# L-1K1W1007851A.net
KiCad netlist of a schematic drawn in Altium Designer
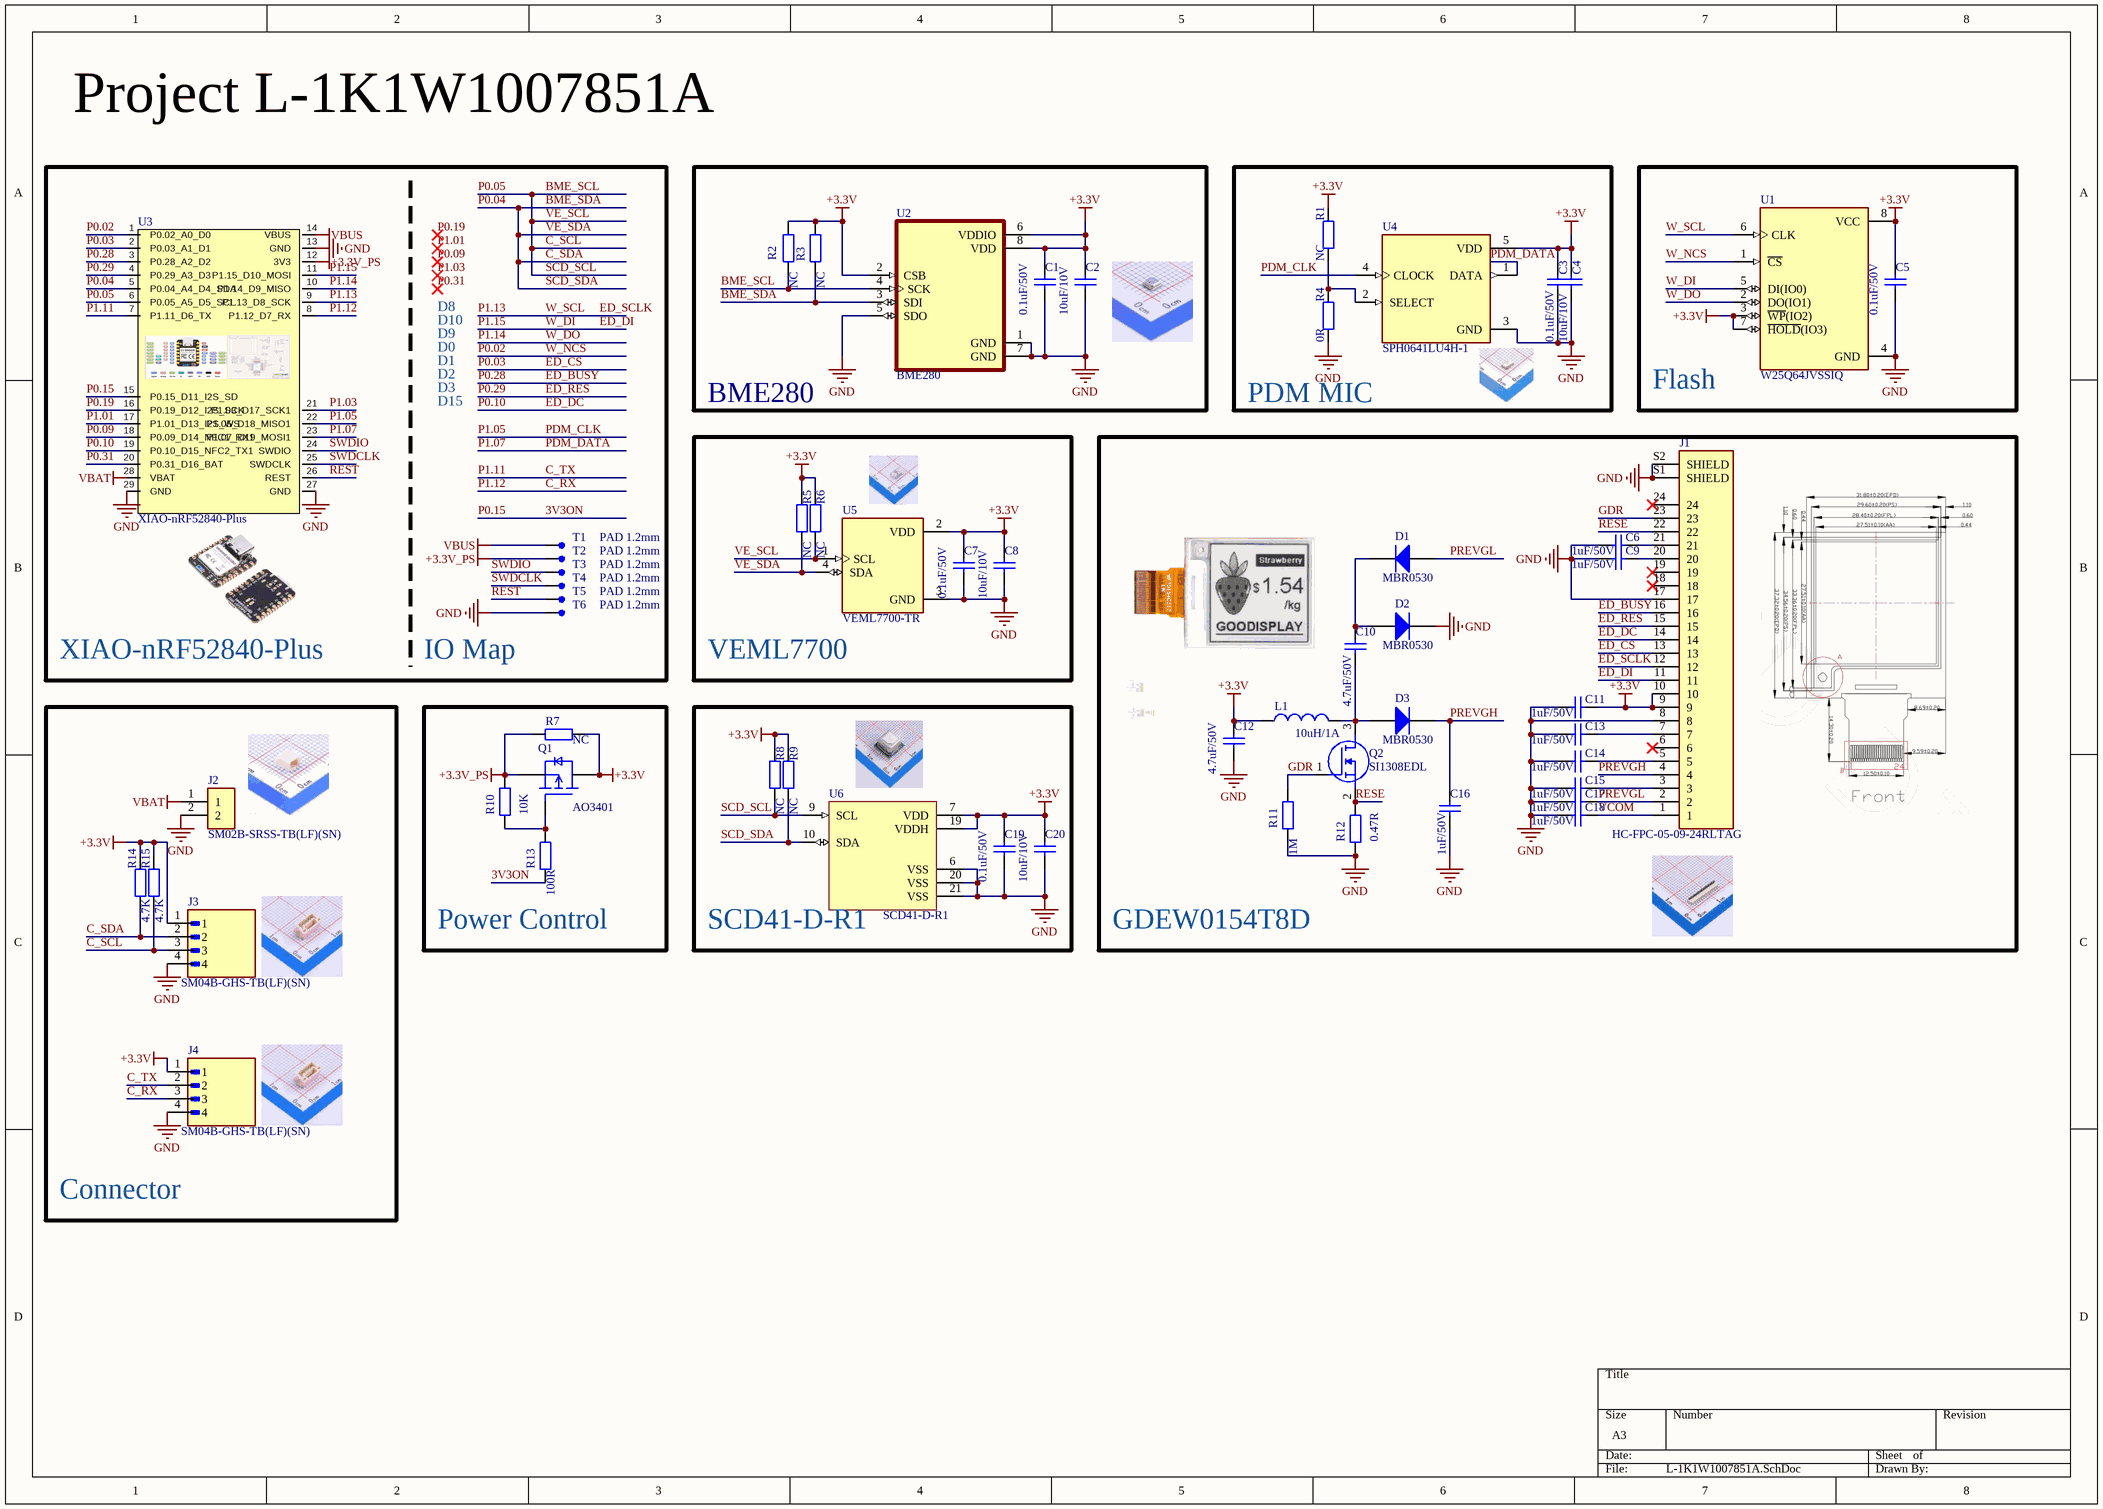
[diagram p0: L-1K1W1007851A.SchDoc]

(export (version "E")
  (design (tool "Eeschema 10.0.6"))
  (components
    (comp (ref "C1") (value "0.1uF/50V") (footprint "C 0603") (libsource (lib "QT") (part "CAP")))
    (comp (ref "C2") (value "10uF/10V") (footprint "C 0603") (libsource (lib "QT") (part "CAP")))
    (comp (ref "C3") (value "0.1uF/50V") (footprint "C 0603") (libsource (lib "QT") (part "CAP")))
    (comp (ref "C4") (value "10uF/10V") (footprint "C 0603") (libsource (lib "QT") (part "CAP")))
    (comp (ref "C5") (value "0.1uF/50V") (footprint "C 0603") (libsource (lib "QT") (part "CAP")))
    (comp (ref "C6") (value "1uF/50V") (footprint "C 0603") (libsource (lib "QT") (part "CAP")))
    (comp (ref "C7") (value "0.1uF/50V") (footprint "C 0603") (libsource (lib "QT") (part "CAP")))
    (comp (ref "C8") (value "10uF/10V") (footprint "C 0603") (libsource (lib "QT") (part "CAP")))
    (comp (ref "C9") (value "1uF/50V") (footprint "C 0603") (libsource (lib "QT") (part "CAP")))
    (comp (ref "C10") (value "4.7uF/50V") (footprint "C 0805") (libsource (lib "QT") (part "CAP")))
    (comp (ref "C11") (value "1uF/50V") (footprint "C 0603") (libsource (lib "QT") (part "CAP")))
    (comp (ref "C12") (value "4.7uF/50V") (footprint "C 0805") (libsource (lib "QT") (part "CAP")))
    (comp (ref "C13") (value "1uF/50V") (footprint "C 0603") (libsource (lib "QT") (part "CAP")))
    (comp (ref "C14") (value "1uF/50V") (footprint "C 0603") (libsource (lib "QT") (part "CAP")))
    (comp (ref "C15") (value "1uF/50V") (footprint "C 0603") (libsource (lib "QT") (part "CAP")))
    (comp (ref "C16") (value "1uF/50V") (footprint "C 0603") (libsource (lib "QT") (part "CAP")))
    (comp (ref "C17") (value "1uF/50V") (footprint "C 0603") (libsource (lib "QT") (part "CAP")))
    (comp (ref "C18") (value "1uF/50V") (footprint "C 0603") (libsource (lib "QT") (part "CAP")))
    (comp (ref "C19") (value "0.1uF/50V") (footprint "C 0603") (libsource (lib "QT") (part "CAP")))
    (comp (ref "C20") (value "10uF/10V") (footprint "C 0603") (libsource (lib "QT") (part "CAP")))
    (comp (ref "D1")
      (value "MBR0530")
      (footprint "SOD-323")
      (description "High Conductance Fast Diode")
      (fields (field (name "PUBLISHER") "Altium Limited"))
      (libsource (lib "QT") (part "D 1N4148"))
    )
    (comp (ref "D2")
      (value "MBR0530")
      (footprint "SOD-323")
      (description "High Conductance Fast Diode")
      (fields (field (name "PUBLISHER") "Altium Limited"))
      (libsource (lib "QT") (part "D 1N4148"))
    )
    (comp (ref "D3")
      (value "MBR0530")
      (footprint "SOD-323")
      (description "High Conductance Fast Diode")
      (fields (field (name "PUBLISHER") "Altium Limited"))
      (libsource (lib "QT") (part "D 1N4148"))
    )
    (comp (ref "J1")
      (value "HC-FPC-05-09-24RLTAG")
      (footprint "GCT_FFC2B28-24-G")
      (description "24 Position FFC, FPC Connector Contacts, Top and Bottom 0.020 (0.50mm) Surface Mount, Right Angle")
      (fields (field (name "MF") "Global Connector Technology") (field (name "MP") "FFC2B28-24-G"))
      (libsource (lib "FFC2B28-24-G") (part "FFC2B28-24-G"))
    )
    (comp (ref "J2")
      (value "SM02B-SRSS-TB(LF)(SN)")
      (footprint "SM02B-SRSS-TB(LF)(SN)")
      (description "Connector Header Surface Mount, Right Angle 2 position 0.039 (1.00mm)")
      (fields (field (name "MF") "JST Sales"))
      (libsource (lib "SM02B-SRSS-TB(LF)(SN)") (part "SM02B-SRSS-TB(LF)(SN)"))
    )
    (comp (ref "J3")
      (value "SM04B-GHS-TB(LF)(SN)")
      (footprint "JST_SM04B-SRSS-TB(LF)(SN)")
      (description "Connector Header Surface Mount, Right Angle 4 position 0.049 (1.25mm)")
      (fields (field (name "MF") "JST Sales America Inc."))
      (libsource (lib "SM04B-GHS-TB(LF)(SN)") (part "SM04B-GHS-TB(LF)(SN)"))
    )
    (comp (ref "J4")
      (value "SM04B-GHS-TB(LF)(SN)")
      (footprint "JST_SM04B-SRSS-TB(LF)(SN)")
      (description "Connector Header Surface Mount, Right Angle 4 position 0.049 (1.25mm)")
      (fields (field (name "MF") "JST Sales America Inc."))
      (libsource (lib "SM04B-GHS-TB(LF)(SN)") (part "SM04B-GHS-TB(LF)(SN)"))
    )
    (comp (ref "L1") (value "10uH/1A") (footprint "CD31") (libsource (lib "QT") (part "INDUCTOR")))
    (comp (ref "Q1")
      (value "AO3401")
      (footprint "SOT23-3N")
      (description "P-Channel 30 V 4A (Ta) 1.4W (Ta) Surface Mount SOT-23-3")
      (fields (field (name "MF") "Alpha & Omega Semiconductor"))
      (libsource (lib "AO3401") (part "AO3401"))
    )
    (comp (ref "Q2")
      (value "SI1308EDL")
      (footprint "SOT323")
      (description "N-Channel 30 V 5.8A (Ta) 1.4W (Ta) Surface Mount SOT-23-3")
      (fields (field (name "MF") "Alpha &") (field (name "MP") "AO3400"))
      (libsource (lib "AO3400") (part "AO3400"))
    )
    (comp (ref "R1")
      (value "NC")
      (footprint "R 0603")
      (description "Resistor")
      (fields (field (name "PUBLISHER") "Altium Limited"))
      (libsource (lib "QT") (part "RES2"))
    )
    (comp (ref "R2")
      (value "NC")
      (footprint "R 0603")
      (description "Resistor")
      (fields (field (name "PUBLISHER") "Altium Limited"))
      (libsource (lib "QT") (part "RES2"))
    )
    (comp (ref "R3")
      (value "NC")
      (footprint "R 0603")
      (description "Resistor")
      (fields (field (name "PUBLISHER") "Altium Limited"))
      (libsource (lib "QT") (part "RES2"))
    )
    (comp (ref "R4")
      (value "0R")
      (footprint "R 0603")
      (description "Resistor")
      (fields (field (name "PUBLISHER") "Altium Limited"))
      (libsource (lib "QT") (part "RES2"))
    )
    (comp (ref "R5")
      (value "NC")
      (footprint "R 0603")
      (description "Resistor")
      (fields (field (name "PUBLISHER") "Altium Limited"))
      (libsource (lib "QT") (part "RES2"))
    )
    (comp (ref "R6")
      (value "NC")
      (footprint "R 0603")
      (description "Resistor")
      (fields (field (name "PUBLISHER") "Altium Limited"))
      (libsource (lib "QT") (part "RES2"))
    )
    (comp (ref "R7")
      (value "NC")
      (footprint "R 0603")
      (description "Resistor")
      (fields (field (name "PUBLISHER") "Altium Limited"))
      (libsource (lib "") (part "RES2_1"))
    )
    (comp (ref "R8")
      (value "NC")
      (footprint "R 0603")
      (description "Resistor")
      (fields (field (name "PUBLISHER") "Altium Limited"))
      (libsource (lib "QT") (part "RES2"))
    )
    (comp (ref "R9")
      (value "NC")
      (footprint "R 0603")
      (description "Resistor")
      (fields (field (name "PUBLISHER") "Altium Limited"))
      (libsource (lib "QT") (part "RES2"))
    )
    (comp (ref "R10")
      (value "10K")
      (footprint "R 0603")
      (description "Resistor")
      (fields (field (name "PUBLISHER") "Altium Limited"))
      (libsource (lib "QT") (part "RES2"))
    )
    (comp (ref "R11")
      (value "1M")
      (footprint "R 0603")
      (description "Resistor")
      (fields (field (name "PUBLISHER") "Altium Limited"))
      (libsource (lib "QT") (part "RES2"))
    )
    (comp (ref "R12")
      (value "0.47R")
      (footprint "R 0603")
      (description "Resistor")
      (fields (field (name "PUBLISHER") "Altium Limited"))
      (libsource (lib "QT") (part "RES2"))
    )
    (comp (ref "R13")
      (value "100R")
      (footprint "R 0603")
      (description "Resistor")
      (fields (field (name "PUBLISHER") "Altium Limited"))
      (libsource (lib "QT") (part "RES2"))
    )
    (comp (ref "R14")
      (value "4.7K")
      (footprint "R 0603")
      (description "Resistor")
      (fields (field (name "PUBLISHER") "Altium Limited"))
      (libsource (lib "QT") (part "RES2"))
    )
    (comp (ref "R15")
      (value "4.7K")
      (footprint "R 0603")
      (description "Resistor")
      (fields (field (name "PUBLISHER") "Altium Limited"))
      (libsource (lib "QT") (part "RES2"))
    )
    (comp (ref "T1") (value "PAD 1.2mm") (footprint "TEST 1.2") (libsource (lib "常用元件库") (part "TEST")))
    (comp (ref "T2") (value "PAD 1.2mm") (footprint "TEST 1.2") (libsource (lib "常用元件库") (part "TEST")))
    (comp (ref "T3") (value "PAD 1.2mm") (footprint "TEST 1.2") (libsource (lib "常用元件库") (part "TEST")))
    (comp (ref "T4") (value "PAD 1.2mm") (footprint "TEST 1.2") (libsource (lib "常用元件库") (part "TEST")))
    (comp (ref "T5") (value "PAD 1.2mm") (footprint "TEST 1.2") (libsource (lib "常用元件库") (part "TEST")))
    (comp (ref "T6") (value "PAD 1.2mm") (footprint "TEST 1.2") (libsource (lib "常用元件库") (part "TEST")))
    (comp (ref "U1")
      (value "W25Q64JVSSIQ")
      (footprint "SOIC127P790X216-8N")
      (description "FLASH - NOR Memory IC 64Mb (8M x 8) SPI 80 MHz 8-SOIC")
      (fields (field (name "MF") "Winbond Electronics") (field (name "MP") "W25Q64BVSSIG"))
      (libsource (lib "W25Q64BVSSIG") (part "W25Q64BVSSIG"))
    )
    (comp (ref "U2")
      (value "BME280")
      (footprint "PSON65P250X250X100-8N")
      (libsource (lib "BME280") (part "BME280"))
    )
    (comp (ref "U3")
      (value "XIAO-nRF52840-Plus")
      (footprint "XIAO-nRF52840-Plus")
      (libsource (lib "XIAO-nRF52840-Plus") (part "XIAO-nRF52840-Plus"))
    )
    (comp (ref "U4")
      (value "SPH0641LU4H-1")
      (footprint "MIC_SPH0641LU4H-1")
      (fields (field (name "MF") "Knowles"))
      (libsource (lib "SPH0641LU4H-1") (part "SPH0641LU4H-1"))
    )
    (comp (ref "U5")
      (value "VEML7700-TR")
      (footprint "XDCR_VEML7700-TR")
      (description "Optical Sensor Ambient 545nm I2C 4-SMD, J-Lead")
      (fields (field (name "MF") "Vishay"))
      (libsource (lib "VEML7700-TR") (part "VEML7700-TR"))
    )
    (comp (ref "U6") (value "SCD41-D-R1") (footprint "SCD4x") (libsource (lib "SCD41-D-R1") (part "SCD4x")))
  )
  (nets
    (net (code "1") (name "+3.3V") (class "Default")
      (node (ref "C1") (pin "2") (pinfunction "2_2") (pintype "passive"))
      (node (ref "C11") (pin "1") (pinfunction "1_1") (pintype "passive"))
      (node (ref "C12") (pin "2") (pinfunction "2_2") (pintype "passive"))
      (node (ref "C19") (pin "2") (pinfunction "2_2") (pintype "passive"))
      (node (ref "C2") (pin "2") (pinfunction "2_2") (pintype "passive"))
      (node (ref "C20") (pin "2") (pinfunction "2_2") (pintype "passive"))
      (node (ref "C3") (pin "2") (pinfunction "2_2") (pintype "passive"))
      (node (ref "C4") (pin "2") (pinfunction "2_2") (pintype "passive"))
      (node (ref "C5") (pin "2") (pinfunction "2_2") (pintype "passive"))
      (node (ref "C7") (pin "2") (pinfunction "2_2") (pintype "passive"))
      (node (ref "C8") (pin "2") (pinfunction "2_2") (pintype "passive"))
      (node (ref "J1") (pin "10") (pinfunction "10_10") (pintype "passive"))
      (node (ref "J1") (pin "9") (pinfunction "9_9") (pintype "passive"))
      (node (ref "J3") (pin "1") (pinfunction "1_1") (pintype "passive"))
      (node (ref "J4") (pin "1") (pinfunction "1_1") (pintype "passive"))
      (node (ref "L1") (pin "1") (pinfunction "1_1") (pintype "passive"))
      (node (ref "Q1") (pin "3") (pinfunction "D_3") (pintype "passive"))
      (node (ref "R1") (pin "1") (pinfunction "1_1") (pintype "passive"))
      (node (ref "R14") (pin "1") (pinfunction "1_1") (pintype "passive"))
      (node (ref "R15") (pin "1") (pinfunction "1_1") (pintype "passive"))
      (node (ref "R2") (pin "1") (pinfunction "1_1") (pintype "passive"))
      (node (ref "R3") (pin "1") (pinfunction "1_1") (pintype "passive"))
      (node (ref "R5") (pin "1") (pinfunction "1_1") (pintype "passive"))
      (node (ref "R6") (pin "1") (pinfunction "1_1") (pintype "passive"))
      (node (ref "R7") (pin "2") (pinfunction "2_2") (pintype "passive"))
      (node (ref "R8") (pin "1") (pinfunction "1_1") (pintype "passive"))
      (node (ref "R9") (pin "1") (pinfunction "1_1") (pintype "passive"))
      (node (ref "U1") (pin "3") (pinfunction "~{WP}(IO2)_3") (pintype "bidirectional"))
      (node (ref "U1") (pin "7") (pinfunction "~{HOLD}(IO3)_7") (pintype "bidirectional"))
      (node (ref "U1") (pin "8") (pinfunction "VCC_8") (pintype "power_in"))
      (node (ref "U2") (pin "2") (pinfunction "CSB_2") (pintype "input"))
      (node (ref "U2") (pin "6") (pinfunction "VDDIO_6") (pintype "power_in"))
      (node (ref "U2") (pin "8") (pinfunction "VDD_8") (pintype "power_in"))
      (node (ref "U4") (pin "5") (pinfunction "VDD_5") (pintype "power_in"))
      (node (ref "U5") (pin "2") (pinfunction "VDD_2") (pintype "power_in"))
      (node (ref "U6") (pin "19") (pinfunction "VDDH_19") (pintype "power_in"))
      (node (ref "U6") (pin "7") (pinfunction "VDD_7") (pintype "power_in"))
    )
    (net (code "2") (name "+3.3V_PS") (class "Default")
      (node (ref "Q1") (pin "2") (pinfunction "S_2") (pintype "passive"))
      (node (ref "R10") (pin "1") (pinfunction "1_1") (pintype "passive"))
      (node (ref "R7") (pin "1") (pinfunction "1_1") (pintype "passive"))
      (node (ref "T2") (pin "1") (pintype "passive"))
      (node (ref "U3") (pin "12") (pinfunction "3V3_12") (pintype "passive"))
    )
    (net (code "3") (name "/3V3ON") (class "Default")
      (node (ref "R13") (pin "2") (pinfunction "2_2") (pintype "passive"))
      (node (ref "U3") (pin "15") (pinfunction "P0.15_D11_I2S_SD_15") (pintype "passive"))
    )
    (net (code "4") (name "/BME_SCL") (class "Default")
      (node (ref "J3") (pin "3") (pinfunction "3_3") (pintype "passive"))
      (node (ref "R14") (pin "2") (pinfunction "2_2") (pintype "passive"))
      (node (ref "R2") (pin "2") (pinfunction "2_2") (pintype "passive"))
      (node (ref "R6") (pin "2") (pinfunction "2_2") (pintype "passive"))
      (node (ref "R8") (pin "2") (pinfunction "2_2") (pintype "passive"))
      (node (ref "U2") (pin "4") (pinfunction "SCK_4") (pintype "input"))
      (node (ref "U3") (pin "6") (pinfunction "P0.05_A5_D5_SCL_6") (pintype "passive"))
      (node (ref "U5") (pin "1") (pinfunction "SCL_1") (pintype "input"))
      (node (ref "U6") (pin "9") (pinfunction "SCL_9") (pintype "input"))
    )
    (net (code "5") (name "/BME_SDA") (class "Default")
      (node (ref "J3") (pin "2") (pinfunction "2_2") (pintype "passive"))
      (node (ref "R15") (pin "2") (pinfunction "2_2") (pintype "passive"))
      (node (ref "R3") (pin "2") (pinfunction "2_2") (pintype "passive"))
      (node (ref "R5") (pin "2") (pinfunction "2_2") (pintype "passive"))
      (node (ref "R9") (pin "2") (pinfunction "2_2") (pintype "passive"))
      (node (ref "U2") (pin "3") (pinfunction "SDI_3") (pintype "bidirectional"))
      (node (ref "U3") (pin "5") (pinfunction "P0.04_A4_D4_SDA_5") (pintype "passive"))
      (node (ref "U5") (pin "4") (pinfunction "SDA_4") (pintype "bidirectional"))
      (node (ref "U6") (pin "10") (pinfunction "SDA_10") (pintype "bidirectional"))
    )
    (net (code "6") (name "/C_RX") (class "Default")
      (node (ref "J4") (pin "3") (pinfunction "3_3") (pintype "passive"))
      (node (ref "U3") (pin "8") (pinfunction "P1.12_D7_RX_8") (pintype "passive"))
    )
    (net (code "7") (name "/C_TX") (class "Default")
      (node (ref "J4") (pin "2") (pinfunction "2_2") (pintype "passive"))
      (node (ref "U3") (pin "7") (pinfunction "P1.11_D6_TX_7") (pintype "passive"))
    )
    (net (code "8") (name "/ED_BUSY") (class "Default")
      (node (ref "J1") (pin "16") (pinfunction "16_16") (pintype "passive"))
      (node (ref "U3") (pin "3") (pinfunction "P0.28_A2_D2_3") (pintype "passive"))
    )
    (net (code "9") (name "/ED_CS") (class "Default")
      (node (ref "J1") (pin "13") (pinfunction "13_13") (pintype "passive"))
      (node (ref "U3") (pin "2") (pinfunction "P0.03_A1_D1_2") (pintype "passive"))
    )
    (net (code "10") (name "/ED_DC") (class "Default")
      (node (ref "J1") (pin "14") (pinfunction "14_14") (pintype "passive"))
      (node (ref "U3") (pin "19") (pinfunction "P0.10_D15_NFC2_TX1_19") (pintype "passive"))
    )
    (net (code "11") (name "/ED_DI") (class "Default")
      (node (ref "J1") (pin "11") (pinfunction "11_11") (pintype "passive"))
      (node (ref "U1") (pin "5") (pinfunction "DI(IO0)_5") (pintype "bidirectional"))
      (node (ref "U3") (pin "11") (pinfunction "P1.15_D10_MOSI_11") (pintype "passive"))
    )
    (net (code "12") (name "/ED_RES") (class "Default")
      (node (ref "J1") (pin "15") (pinfunction "15_15") (pintype "passive"))
      (node (ref "U3") (pin "4") (pinfunction "P0.29_A3_D3_4") (pintype "passive"))
    )
    (net (code "13") (name "/ED_SCLK") (class "Default")
      (node (ref "J1") (pin "12") (pinfunction "12_12") (pintype "passive"))
      (node (ref "U1") (pin "6") (pinfunction "CLK_6") (pintype "input"))
      (node (ref "U3") (pin "9") (pinfunction "P1.13_D8_SCK_9") (pintype "passive"))
    )
    (net (code "14") (name "/GDR") (class "Default")
      (node (ref "J1") (pin "23") (pinfunction "23_23") (pintype "passive"))
      (node (ref "Q2") (pin "1") (pinfunction "G_1") (pintype "passive"))
      (node (ref "R11") (pin "1") (pinfunction "1_1") (pintype "passive"))
    )
    (net (code "15") (name "/P0.02") (class "Default")
      (node (ref "U1") (pin "1") (pinfunction "~{CS}_1") (pintype "input"))
      (node (ref "U3") (pin "1") (pinfunction "P0.02_A0_D0_1") (pintype "passive"))
    )
    (net (code "16") (name "/P0.09") (class "Default")
      (node (ref "U3") (pin "18") (pinfunction "P0.09_D14_NFC1_RX1_18") (pintype "passive+no_connect"))
    )
    (net (code "17") (name "/P0.19") (class "Default")
      (node (ref "U3") (pin "16") (pinfunction "P0.19_D12_I2S_SCK_16") (pintype "passive+no_connect"))
    )
    (net (code "18") (name "/P0.31") (class "Default")
      (node (ref "U3") (pin "20") (pinfunction "P0.31_D16_BAT_20") (pintype "passive+no_connect"))
    )
    (net (code "19") (name "/P1.01") (class "Default")
      (node (ref "U3") (pin "17") (pinfunction "P1.01_D13_I2S_WS_17") (pintype "passive+no_connect"))
    )
    (net (code "20") (name "/P1.03") (class "Default")
      (node (ref "U3") (pin "21") (pinfunction "P1.03_D17_SCK1_21") (pintype "passive+no_connect"))
    )
    (net (code "21") (name "/P1.05") (class "Default")
      (node (ref "U3") (pin "22") (pinfunction "P1.05_D18_MISO1_22") (pintype "passive"))
      (node (ref "U4") (pin "4") (pinfunction "CLOCK_4") (pintype "input"))
    )
    (net (code "22") (name "/P1.07") (class "Default")
      (node (ref "U3") (pin "23") (pinfunction "P1.07_D19_MOSI1_23") (pintype "passive"))
      (node (ref "U4") (pin "1") (pinfunction "DATA_1") (pintype "output"))
    )
    (net (code "23") (name "/P1.14") (class "Default")
      (node (ref "U1") (pin "2") (pinfunction "DO(IO1)_2") (pintype "bidirectional"))
      (node (ref "U3") (pin "10") (pinfunction "P1.14_D9_MISO_10") (pintype "passive"))
    )
    (net (code "24") (name "/PREVGH") (class "Default")
      (node (ref "C16") (pin "2") (pinfunction "2_2") (pintype "passive"))
      (node (ref "D3") (pin "2") (pinfunction "K_2") (pintype "passive"))
      (node (ref "J1") (pin "4") (pinfunction "4_4") (pintype "passive"))
    )
    (net (code "25") (name "/PREVGL") (class "Default")
      (node (ref "C17") (pin "1") (pinfunction "1_1") (pintype "passive"))
      (node (ref "D1") (pin "1") (pinfunction "A_1") (pintype "passive"))
      (node (ref "J1") (pin "2") (pinfunction "2_2") (pintype "passive"))
    )
    (net (code "26") (name "/RESE") (class "Default")
      (node (ref "J1") (pin "22") (pinfunction "22_22") (pintype "passive"))
      (node (ref "Q2") (pin "2") (pinfunction "S_2") (pintype "passive"))
      (node (ref "R12") (pin "1") (pinfunction "1_1") (pintype "passive"))
    )
    (net (code "27") (name "/REST") (class "Default")
      (node (ref "T5") (pin "1") (pintype "passive"))
      (node (ref "U3") (pin "26") (pinfunction "REST_26") (pintype "passive"))
    )
    (net (code "28") (name "/SWDCLK") (class "Default")
      (node (ref "T4") (pin "1") (pintype "passive"))
      (node (ref "U3") (pin "25") (pinfunction "SWDCLK_25") (pintype "passive"))
    )
    (net (code "29") (name "/SWDIO") (class "Default")
      (node (ref "T3") (pin "1") (pintype "passive"))
      (node (ref "U3") (pin "24") (pinfunction "SWDIO_24") (pintype "passive"))
    )
    (net (code "30") (name "/VCOM") (class "Default")
      (node (ref "C18") (pin "1") (pinfunction "1_1") (pintype "passive"))
      (node (ref "J1") (pin "1") (pinfunction "1_1") (pintype "passive"))
    )
    (net (code "31") (name "GND") (class "Default")
      (node (ref "C1") (pin "1") (pinfunction "1_1") (pintype "passive"))
      (node (ref "C11") (pin "2") (pinfunction "2_2") (pintype "passive"))
      (node (ref "C12") (pin "1") (pinfunction "1_1") (pintype "passive"))
      (node (ref "C13") (pin "2") (pinfunction "2_2") (pintype "passive"))
      (node (ref "C14") (pin "2") (pinfunction "2_2") (pintype "passive"))
      (node (ref "C15") (pin "2") (pinfunction "2_2") (pintype "passive"))
      (node (ref "C16") (pin "1") (pinfunction "1_1") (pintype "passive"))
      (node (ref "C17") (pin "2") (pinfunction "2_2") (pintype "passive"))
      (node (ref "C18") (pin "2") (pinfunction "2_2") (pintype "passive"))
      (node (ref "C19") (pin "1") (pinfunction "1_1") (pintype "passive"))
      (node (ref "C2") (pin "1") (pinfunction "1_1") (pintype "passive"))
      (node (ref "C20") (pin "1") (pinfunction "1_1") (pintype "passive"))
      (node (ref "C3") (pin "1") (pinfunction "1_1") (pintype "passive"))
      (node (ref "C4") (pin "1") (pinfunction "1_1") (pintype "passive"))
      (node (ref "C5") (pin "1") (pinfunction "1_1") (pintype "passive"))
      (node (ref "C6") (pin "2") (pinfunction "2_2") (pintype "passive"))
      (node (ref "C7") (pin "1") (pinfunction "1_1") (pintype "passive"))
      (node (ref "C8") (pin "1") (pinfunction "1_1") (pintype "passive"))
      (node (ref "C9") (pin "2") (pinfunction "2_2") (pintype "passive"))
      (node (ref "D2") (pin "2") (pinfunction "K_2") (pintype "passive"))
      (node (ref "J1") (pin "17") (pinfunction "17_17") (pintype "passive"))
      (node (ref "J1") (pin "8") (pinfunction "8_8") (pintype "passive"))
      (node (ref "J1") (pin "S1") (pinfunction "SHIELD_S1") (pintype "passive"))
      (node (ref "J1") (pin "S2") (pinfunction "SHIELD_S2") (pintype "passive"))
      (node (ref "J2") (pin "2") (pinfunction "2_2") (pintype "power_in"))
      (node (ref "J3") (pin "4") (pinfunction "4_4") (pintype "passive"))
      (node (ref "J4") (pin "4") (pinfunction "4_4") (pintype "passive"))
      (node (ref "R11") (pin "2") (pinfunction "2_2") (pintype "passive"))
      (node (ref "R12") (pin "2") (pinfunction "2_2") (pintype "passive"))
      (node (ref "R4") (pin "2") (pinfunction "2_2") (pintype "passive"))
      (node (ref "T6") (pin "1") (pintype "passive"))
      (node (ref "U1") (pin "4") (pinfunction "GND_4") (pintype "power_in"))
      (node (ref "U2") (pin "1") (pinfunction "GND_1") (pintype "passive"))
      (node (ref "U2") (pin "5") (pinfunction "SDO_5") (pintype "bidirectional"))
      (node (ref "U2") (pin "7") (pinfunction "GND_7") (pintype "passive"))
      (node (ref "U3") (pin "13") (pinfunction "GND_13") (pintype "passive"))
      (node (ref "U3") (pin "27") (pinfunction "GND_27") (pintype "passive"))
      (node (ref "U3") (pin "29") (pinfunction "GND_29") (pintype "passive"))
      (node (ref "U4") (pin "3") (pinfunction "GND_3") (pintype "power_in"))
      (node (ref "U5") (pin "3") (pinfunction "GND_3") (pintype "power_in"))
      (node (ref "U6") (pin "20") (pinfunction "VSS_20") (pintype "power_in"))
      (node (ref "U6") (pin "21") (pinfunction "VSS_21") (pintype "power_in"))
      (node (ref "U6") (pin "6") (pinfunction "VSS_6") (pintype "power_in"))
    )
    (net (code "32") (name "Net-(C6-Pad1)") (class "Default")
      (node (ref "C6") (pin "1") (pinfunction "1_1") (pintype "passive"))
      (node (ref "J1") (pin "21") (pinfunction "21_21") (pintype "passive"))
    )
    (net (code "33") (name "Net-(C9-Pad1)") (class "Default")
      (node (ref "C9") (pin "1") (pinfunction "1_1") (pintype "passive"))
      (node (ref "J1") (pin "20") (pinfunction "20_20") (pintype "passive"))
    )
    (net (code "34") (name "Net-(C13-Pad1)") (class "Default")
      (node (ref "C13") (pin "1") (pinfunction "1_1") (pintype "passive"))
      (node (ref "J1") (pin "7") (pinfunction "7_7") (pintype "passive"))
    )
    (net (code "35") (name "Net-(C14-Pad1)") (class "Default")
      (node (ref "C14") (pin "1") (pinfunction "1_1") (pintype "passive"))
      (node (ref "J1") (pin "5") (pinfunction "5_5") (pintype "passive"))
    )
    (net (code "36") (name "Net-(C15-Pad1)") (class "Default")
      (node (ref "C15") (pin "1") (pinfunction "1_1") (pintype "passive"))
      (node (ref "J1") (pin "3") (pinfunction "3_3") (pintype "passive"))
    )
    (net (code "37") (name "Net-(D1-K)") (class "Default")
      (node (ref "C10") (pin "2") (pinfunction "2_2") (pintype "passive"))
      (node (ref "D1") (pin "2") (pinfunction "K_2") (pintype "passive"))
      (node (ref "D2") (pin "1") (pinfunction "A_1") (pintype "passive"))
    )
    (net (code "38") (name "Net-(D3-A)") (class "Default")
      (node (ref "C10") (pin "1") (pinfunction "1_1") (pintype "passive"))
      (node (ref "D3") (pin "1") (pinfunction "A_1") (pintype "passive"))
      (node (ref "L1") (pin "2") (pinfunction "2_2") (pintype "passive"))
      (node (ref "Q2") (pin "3") (pinfunction "D_3") (pintype "passive"))
    )
    (net (code "39") (name "Net-(Q1-G)") (class "Default")
      (node (ref "Q1") (pin "1") (pinfunction "G_1") (pintype "passive"))
      (node (ref "R10") (pin "2") (pinfunction "2_2") (pintype "passive"))
      (node (ref "R13") (pin "1") (pinfunction "1_1") (pintype "passive"))
    )
    (net (code "40") (name "Net-(U4-SELECT)") (class "Default")
      (node (ref "R1") (pin "2") (pinfunction "2_2") (pintype "passive"))
      (node (ref "R4") (pin "1") (pinfunction "1_1") (pintype "passive"))
      (node (ref "U4") (pin "2") (pinfunction "SELECT_2") (pintype "input"))
    )
    (net (code "41") (name "VBAT") (class "Default")
      (node (ref "J2") (pin "1") (pinfunction "1_1") (pintype "power_in"))
      (node (ref "U3") (pin "28") (pinfunction "VBAT_28") (pintype "passive"))
    )
    (net (code "42") (name "VBUS") (class "Default")
      (node (ref "T1") (pin "1") (pintype "passive"))
      (node (ref "U3") (pin "14") (pinfunction "VBUS_14") (pintype "passive"))
    )
    (net (code "43") (name "unconnected-(J1-Pad6)") (class "Default")
      (node (ref "J1") (pin "6") (pinfunction "6_6") (pintype "passive+no_connect"))
    )
    (net (code "44") (name "unconnected-(J1-Pad18)") (class "Default")
      (node (ref "J1") (pin "18") (pinfunction "18_18") (pintype "passive+no_connect"))
    )
    (net (code "45") (name "unconnected-(J1-Pad19)") (class "Default")
      (node (ref "J1") (pin "19") (pinfunction "19_19") (pintype "passive+no_connect"))
    )
    (net (code "46") (name "unconnected-(J1-Pad24)") (class "Default")
      (node (ref "J1") (pin "24") (pinfunction "24_24") (pintype "passive+no_connect"))
    )
  )
)
